# SCH_Tiny_printer_small_screen_2024-12-15.net
KiCad netlist of a schematic drawn in EasyEDA
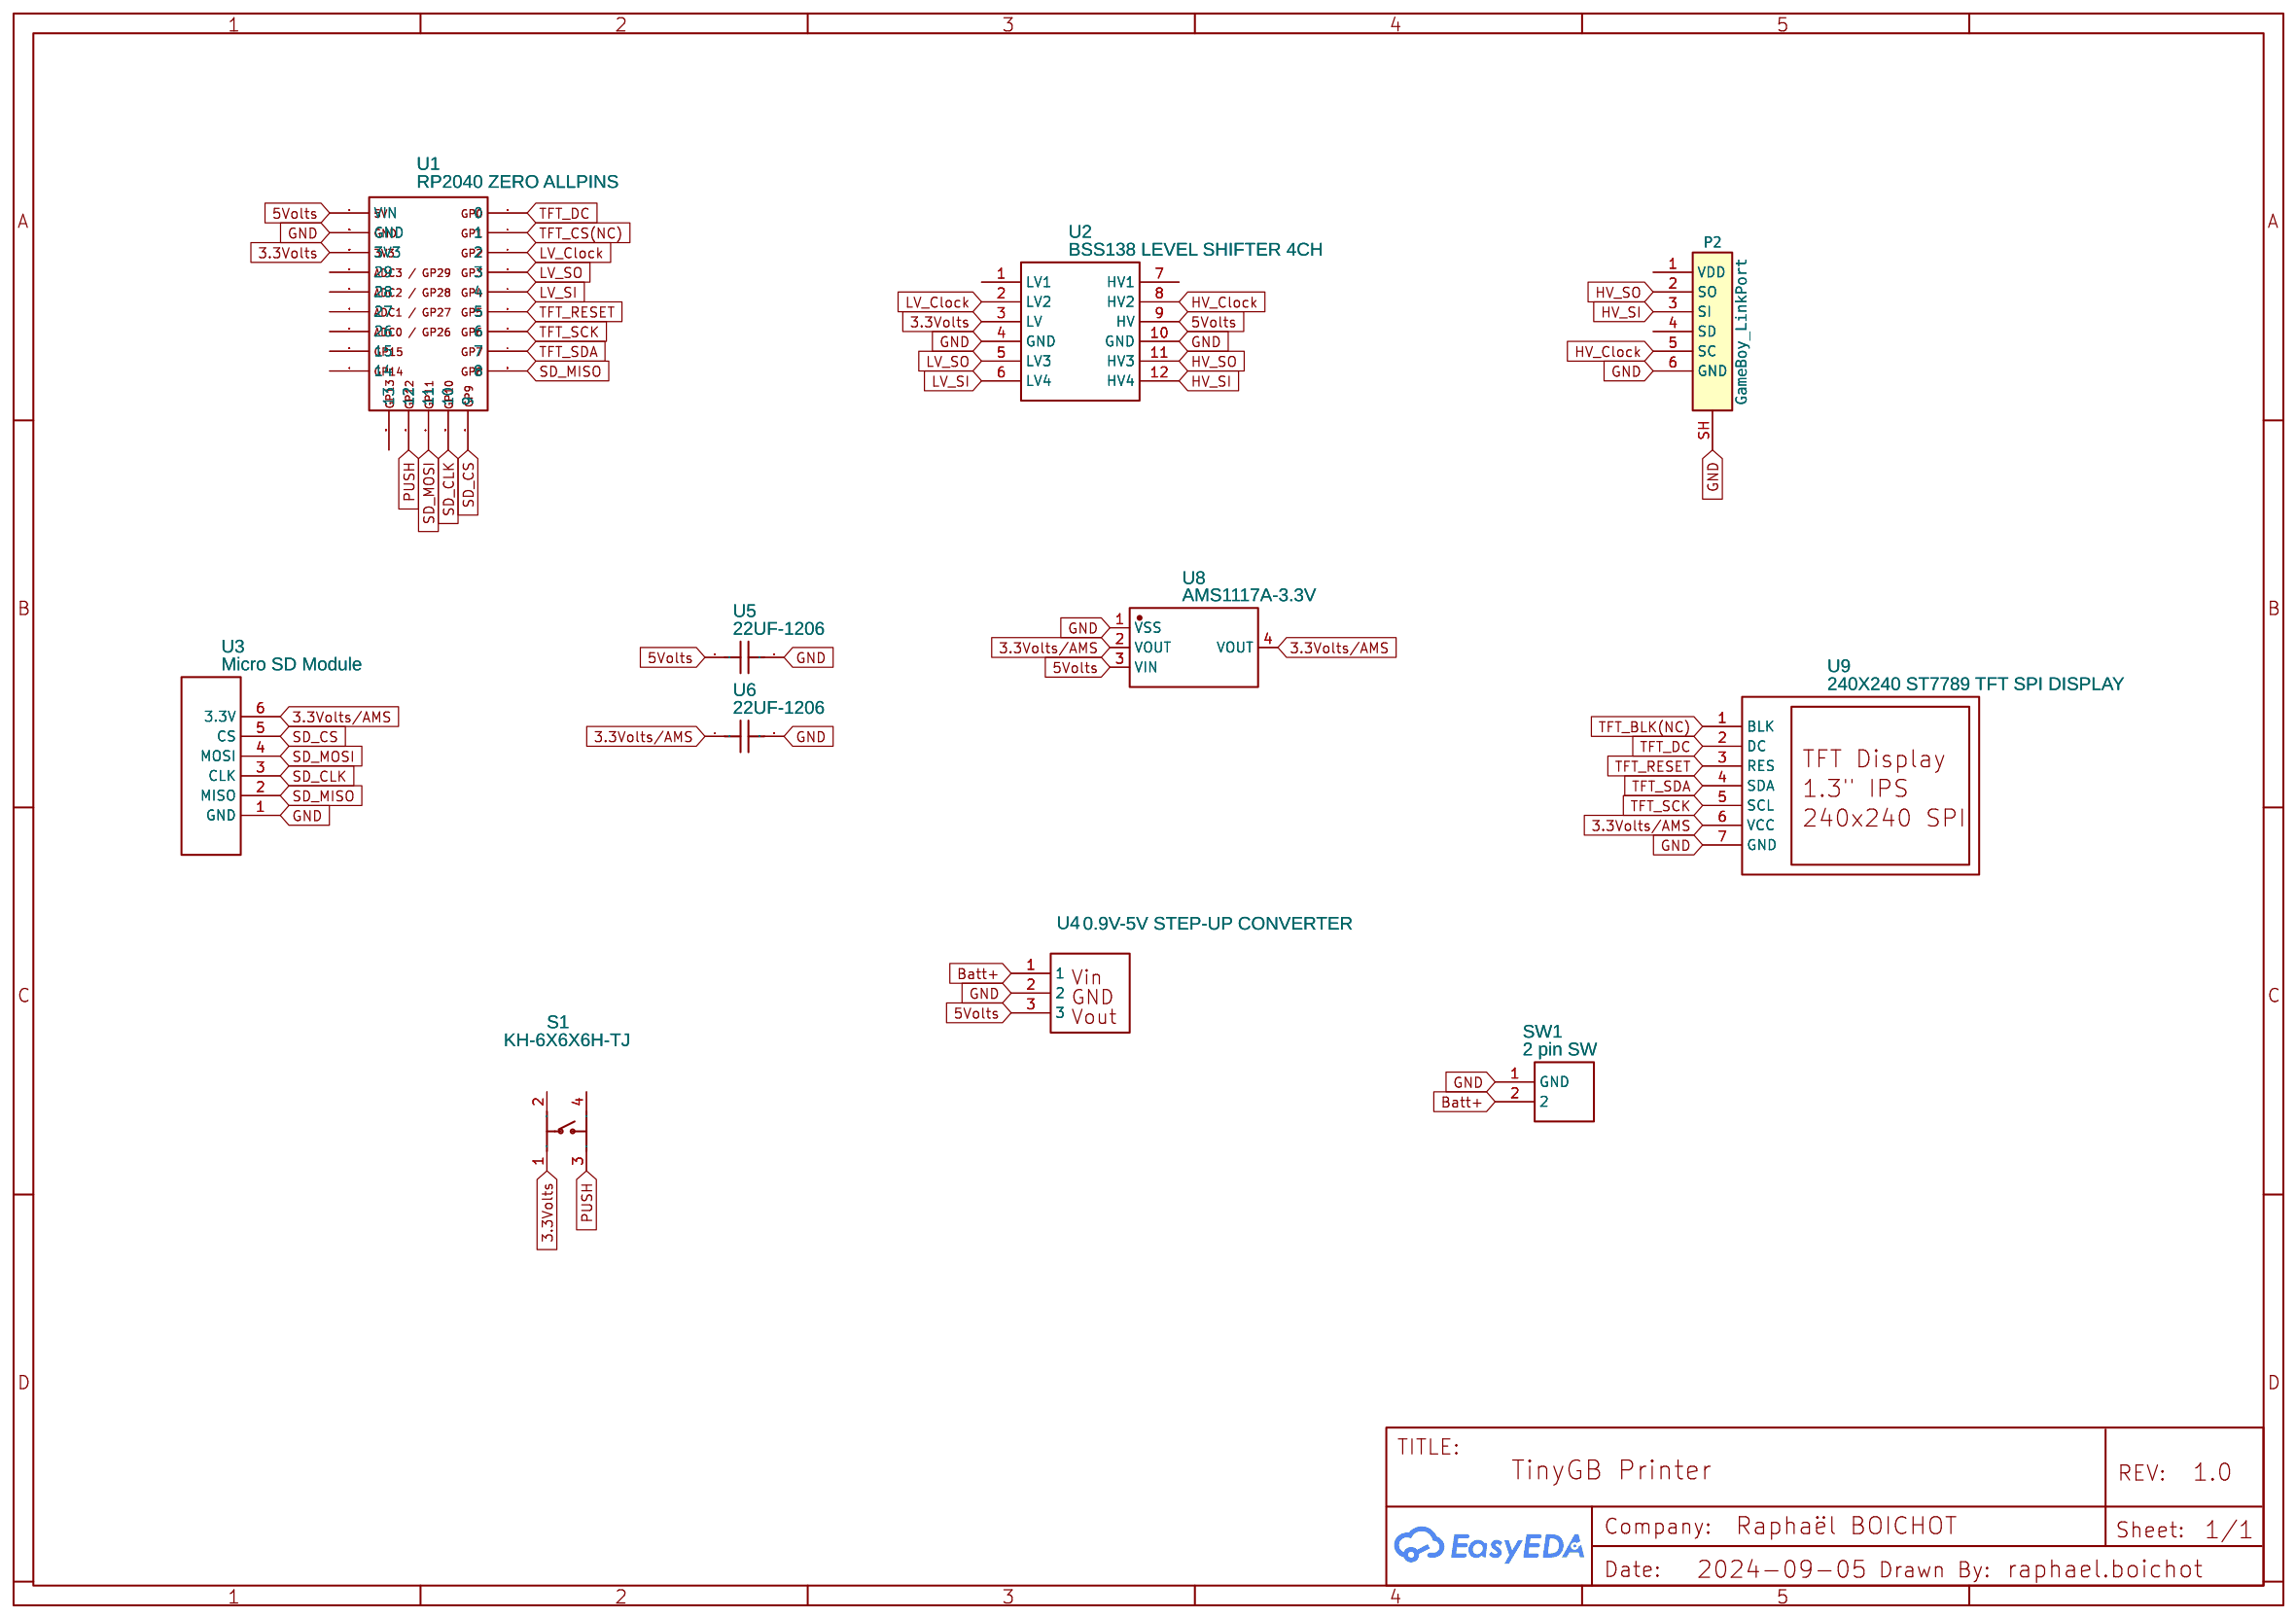
[diagram p0: schematic sheet]

(export (version "E")
  (design (tool "Eeschema 10.0.6"))
  (components
    (comp (ref "P2") (value "GameBoy_LinkPort") (libsource (lib "") (part "Unknown_860_-645")))
    (comp (ref "S1")
      (value "KH-6X6X6H-TJ")
      (fields (field (name "Manufacturer") "kinghelm(金航标)"))
      (libsource (lib "") (part "KH-6X6X6H-TJ"))
    )
    (comp (ref "SW1")
      (value "2 pin SW")
      (fields (field (name "Manufacturer") "NA"))
      (libsource (lib "") (part "2 pin SW"))
    )
    (comp (ref "U1")
      (value "RP2040 ZERO ALLPINS")
      (fields (field (name "Manufacturer Part") "RP2040 Zero") (field (name "Manufacturer") "Waveshare"))
      (libsource (lib "") (part "RP2040 ZERO ALLPINS"))
    )
    (comp (ref "U2")
      (value "BSS138 LEVEL SHIFTER 4CH")
      (fields (field (name "Manufacturer Part") "BSS138") (field (name "Manufacturer") "ON Semiconductor"))
      (libsource (lib "") (part "BSS138 LEVEL SHIFTER 4CH"))
    )
    (comp (ref "U3") (value "Micro SD Module") (libsource (lib "") (part "Micro SD Module")))
    (comp (ref "U4")
      (value "0.9V-5V STEP-UP CONVERTER")
      (fields (field (name "Manufacturer") "Generic"))
      (libsource (lib "") (part "0.9V-5V STEP-UP CONVERTER"))
    )
    (comp (ref "U5")
      (value "22UF-1206")
      (fields (field (name "Manufacturer Part") "220UF-1206"))
      (libsource (lib "") (part "220UF-1206"))
    )
    (comp (ref "U6")
      (value "22UF-1206")
      (fields (field (name "Manufacturer Part") "220UF-1206"))
      (libsource (lib "") (part "220UF-1206"))
    )
    (comp (ref "U8")
      (value "AMS1117A-3.3V")
      (fields (field (name "Manufacturer") "HX(恒佳兴)"))
      (libsource (lib "") (part "AMS1117A-3.3V"))
    )
    (comp (ref "U9")
      (value "240X240 ST7789 TFT SPI DISPLAY")
      (libsource (lib "") (part "240X240 ST7789 TFT SPI DISPLAY"))
    )
  )
  (nets
    (net (code "1") (name "3.3Volts") (class "Default")
      (node (ref "S1") (pin "1") (pinfunction "1_1") (pintype "unspecified"))
      (node (ref "U1") (pin "3V3") (pinfunction "3V3_3V3") (pintype "unspecified"))
      (node (ref "U2") (pin "3") (pinfunction "LV_3") (pintype "passive"))
    )
    (net (code "2") (name "3.3Volts{slash}AMS") (class "Default")
      (node (ref "U3") (pin "6") (pinfunction "3.3V_6") (pintype "unspecified"))
      (node (ref "U6") (pin "1") (pinfunction "1_1") (pintype "unspecified"))
      (node (ref "U8") (pin "2") (pinfunction "VOUT_2") (pintype "unspecified"))
      (node (ref "U8") (pin "4") (pinfunction "VOUT_4") (pintype "unspecified"))
      (node (ref "U9") (pin "6") (pinfunction "VCC_6") (pintype "unspecified"))
    )
    (net (code "3") (name "5Volts") (class "Default")
      (node (ref "U1") (pin "VIN") (pinfunction "VIN_VIN") (pintype "unspecified"))
      (node (ref "U2") (pin "9") (pinfunction "HV_9") (pintype "passive"))
      (node (ref "U4") (pin "3") (pinfunction "3_3") (pintype "unspecified"))
      (node (ref "U5") (pin "1") (pinfunction "1_1") (pintype "unspecified"))
      (node (ref "U8") (pin "3") (pinfunction "VIN_3") (pintype "unspecified"))
    )
    (net (code "4") (name "Batt+") (class "Default")
      (node (ref "SW1") (pin "2") (pinfunction "2_2") (pintype "unspecified"))
      (node (ref "U4") (pin "1") (pinfunction "1_1") (pintype "unspecified"))
    )
    (net (code "5") (name "GND") (class "Default")
      (node (ref "P2") (pin "6") (pinfunction "GND_6") (pintype "unspecified"))
      (node (ref "P2") (pin "SH") (pintype "unspecified"))
      (node (ref "SW1") (pin "1") (pinfunction "GND_1") (pintype "unspecified"))
      (node (ref "U1") (pin "GND") (pinfunction "GND_GND") (pintype "unspecified"))
      (node (ref "U2") (pin "10") (pinfunction "GND_10") (pintype "passive"))
      (node (ref "U2") (pin "4") (pinfunction "GND_4") (pintype "passive"))
      (node (ref "U3") (pin "1") (pinfunction "GND_1") (pintype "unspecified"))
      (node (ref "U4") (pin "2") (pinfunction "2_2") (pintype "unspecified"))
      (node (ref "U5") (pin "2") (pinfunction "2_2") (pintype "unspecified"))
      (node (ref "U6") (pin "2") (pinfunction "2_2") (pintype "unspecified"))
      (node (ref "U8") (pin "1") (pinfunction "VSS_1") (pintype "unspecified"))
      (node (ref "U9") (pin "7") (pinfunction "GND_7") (pintype "unspecified"))
    )
    (net (code "6") (name "HV_Clock") (class "Default")
      (node (ref "P2") (pin "5") (pinfunction "SC_5") (pintype "unspecified"))
      (node (ref "U2") (pin "8") (pinfunction "HV2_8") (pintype "output"))
    )
    (net (code "7") (name "HV_SI") (class "Default")
      (node (ref "P2") (pin "3") (pinfunction "SI_3") (pintype "unspecified"))
      (node (ref "U2") (pin "12") (pinfunction "HV4_12") (pintype "output"))
    )
    (net (code "8") (name "HV_SO") (class "Default")
      (node (ref "P2") (pin "2") (pinfunction "SO_2") (pintype "unspecified"))
      (node (ref "U2") (pin "11") (pinfunction "HV3_11") (pintype "output"))
    )
    (net (code "9") (name "LV_Clock") (class "Default")
      (node (ref "U1") (pin "2") (pinfunction "2_2") (pintype "unspecified"))
      (node (ref "U2") (pin "2") (pinfunction "LV2_2") (pintype "input"))
    )
    (net (code "10") (name "LV_SI") (class "Default")
      (node (ref "U1") (pin "4") (pinfunction "4_4") (pintype "unspecified"))
      (node (ref "U2") (pin "6") (pinfunction "LV4_6") (pintype "input"))
    )
    (net (code "11") (name "LV_SO") (class "Default")
      (node (ref "U1") (pin "3") (pinfunction "3_3") (pintype "unspecified"))
      (node (ref "U2") (pin "5") (pinfunction "LV3_5") (pintype "input"))
    )
    (net (code "12") (name "PUSH") (class "Default")
      (node (ref "S1") (pin "3") (pinfunction "3_3") (pintype "unspecified"))
      (node (ref "U1") (pin "12") (pinfunction "12_12") (pintype "unspecified"))
    )
    (net (code "13") (name "SD_CLK") (class "Default")
      (node (ref "U1") (pin "10") (pinfunction "10_10") (pintype "unspecified"))
      (node (ref "U3") (pin "3") (pinfunction "CLK_3") (pintype "unspecified"))
    )
    (net (code "14") (name "SD_CS") (class "Default")
      (node (ref "U1") (pin "9") (pinfunction "9_9") (pintype "unspecified"))
      (node (ref "U3") (pin "5") (pinfunction "CS_5") (pintype "unspecified"))
    )
    (net (code "15") (name "SD_MISO") (class "Default")
      (node (ref "U1") (pin "8") (pinfunction "8_8") (pintype "unspecified"))
      (node (ref "U3") (pin "2") (pinfunction "MISO_2") (pintype "unspecified"))
    )
    (net (code "16") (name "SD_MOSI") (class "Default")
      (node (ref "U1") (pin "11") (pinfunction "11_11") (pintype "unspecified"))
      (node (ref "U3") (pin "4") (pinfunction "MOSI_4") (pintype "unspecified"))
    )
    (net (code "17") (name "TFT_BLK(NC)") (class "Default")
      (node (ref "U9") (pin "1") (pinfunction "BLK_1") (pintype "unspecified"))
    )
    (net (code "18") (name "TFT_CS(NC)") (class "Default")
      (node (ref "U1") (pin "1") (pinfunction "1_1") (pintype "unspecified"))
    )
    (net (code "19") (name "TFT_DC") (class "Default")
      (node (ref "U1") (pin "0") (pinfunction "0_0") (pintype "unspecified"))
      (node (ref "U9") (pin "2") (pinfunction "DC_2") (pintype "unspecified"))
    )
    (net (code "20") (name "TFT_RESET") (class "Default")
      (node (ref "U1") (pin "5") (pinfunction "5_5") (pintype "unspecified"))
      (node (ref "U9") (pin "3") (pinfunction "RES_3") (pintype "unspecified"))
    )
    (net (code "21") (name "TFT_SCK") (class "Default")
      (node (ref "U1") (pin "6") (pinfunction "6_6") (pintype "unspecified"))
      (node (ref "U9") (pin "5") (pinfunction "SCL_5") (pintype "unspecified"))
    )
    (net (code "22") (name "TFT_SDA") (class "Default")
      (node (ref "U1") (pin "7") (pinfunction "7_7") (pintype "unspecified"))
      (node (ref "U9") (pin "4") (pinfunction "SDA_4") (pintype "unspecified"))
    )
    (net (code "23") (name "unconnected-(P2-SD-Pad4)") (class "Default")
      (node (ref "P2") (pin "4") (pinfunction "SD_4") (pintype "unspecified"))
    )
    (net (code "24") (name "unconnected-(P2-VDD-Pad1)") (class "Default")
      (node (ref "P2") (pin "1") (pinfunction "VDD_1") (pintype "unspecified"))
    )
    (net (code "25") (name "unconnected-(S1-Pad2)") (class "Default")
      (node (ref "S1") (pin "2") (pinfunction "2_2") (pintype "unspecified"))
    )
    (net (code "26") (name "unconnected-(S1-Pad4)") (class "Default")
      (node (ref "S1") (pin "4") (pinfunction "4_4") (pintype "unspecified"))
    )
    (net (code "27") (name "unconnected-(U1-Pad13)") (class "Default")
      (node (ref "U1") (pin "13") (pinfunction "13_13") (pintype "unspecified"))
    )
    (net (code "28") (name "unconnected-(U1-Pad14)") (class "Default")
      (node (ref "U1") (pin "14") (pinfunction "14_14") (pintype "unspecified"))
    )
    (net (code "29") (name "unconnected-(U1-Pad15)") (class "Default")
      (node (ref "U1") (pin "15") (pinfunction "15_15") (pintype "unspecified"))
    )
    (net (code "30") (name "unconnected-(U1-Pad26)") (class "Default")
      (node (ref "U1") (pin "26") (pinfunction "26_26") (pintype "unspecified"))
    )
    (net (code "31") (name "unconnected-(U1-Pad27)") (class "Default")
      (node (ref "U1") (pin "27") (pinfunction "27_27") (pintype "unspecified"))
    )
    (net (code "32") (name "unconnected-(U1-Pad28)") (class "Default")
      (node (ref "U1") (pin "28") (pinfunction "28_28") (pintype "unspecified"))
    )
    (net (code "33") (name "unconnected-(U1-Pad29)") (class "Default")
      (node (ref "U1") (pin "29") (pinfunction "29_29") (pintype "unspecified"))
    )
    (net (code "34") (name "unconnected-(U2-HV1-Pad7)") (class "Default")
      (node (ref "U2") (pin "7") (pinfunction "HV1_7") (pintype "output"))
    )
    (net (code "35") (name "unconnected-(U2-LV1-Pad1)") (class "Default")
      (node (ref "U2") (pin "1") (pinfunction "LV1_1") (pintype "input"))
    )
  )
)
